# QueenSchematics.net
KiCad netlist of a schematic drawn in EAGLE
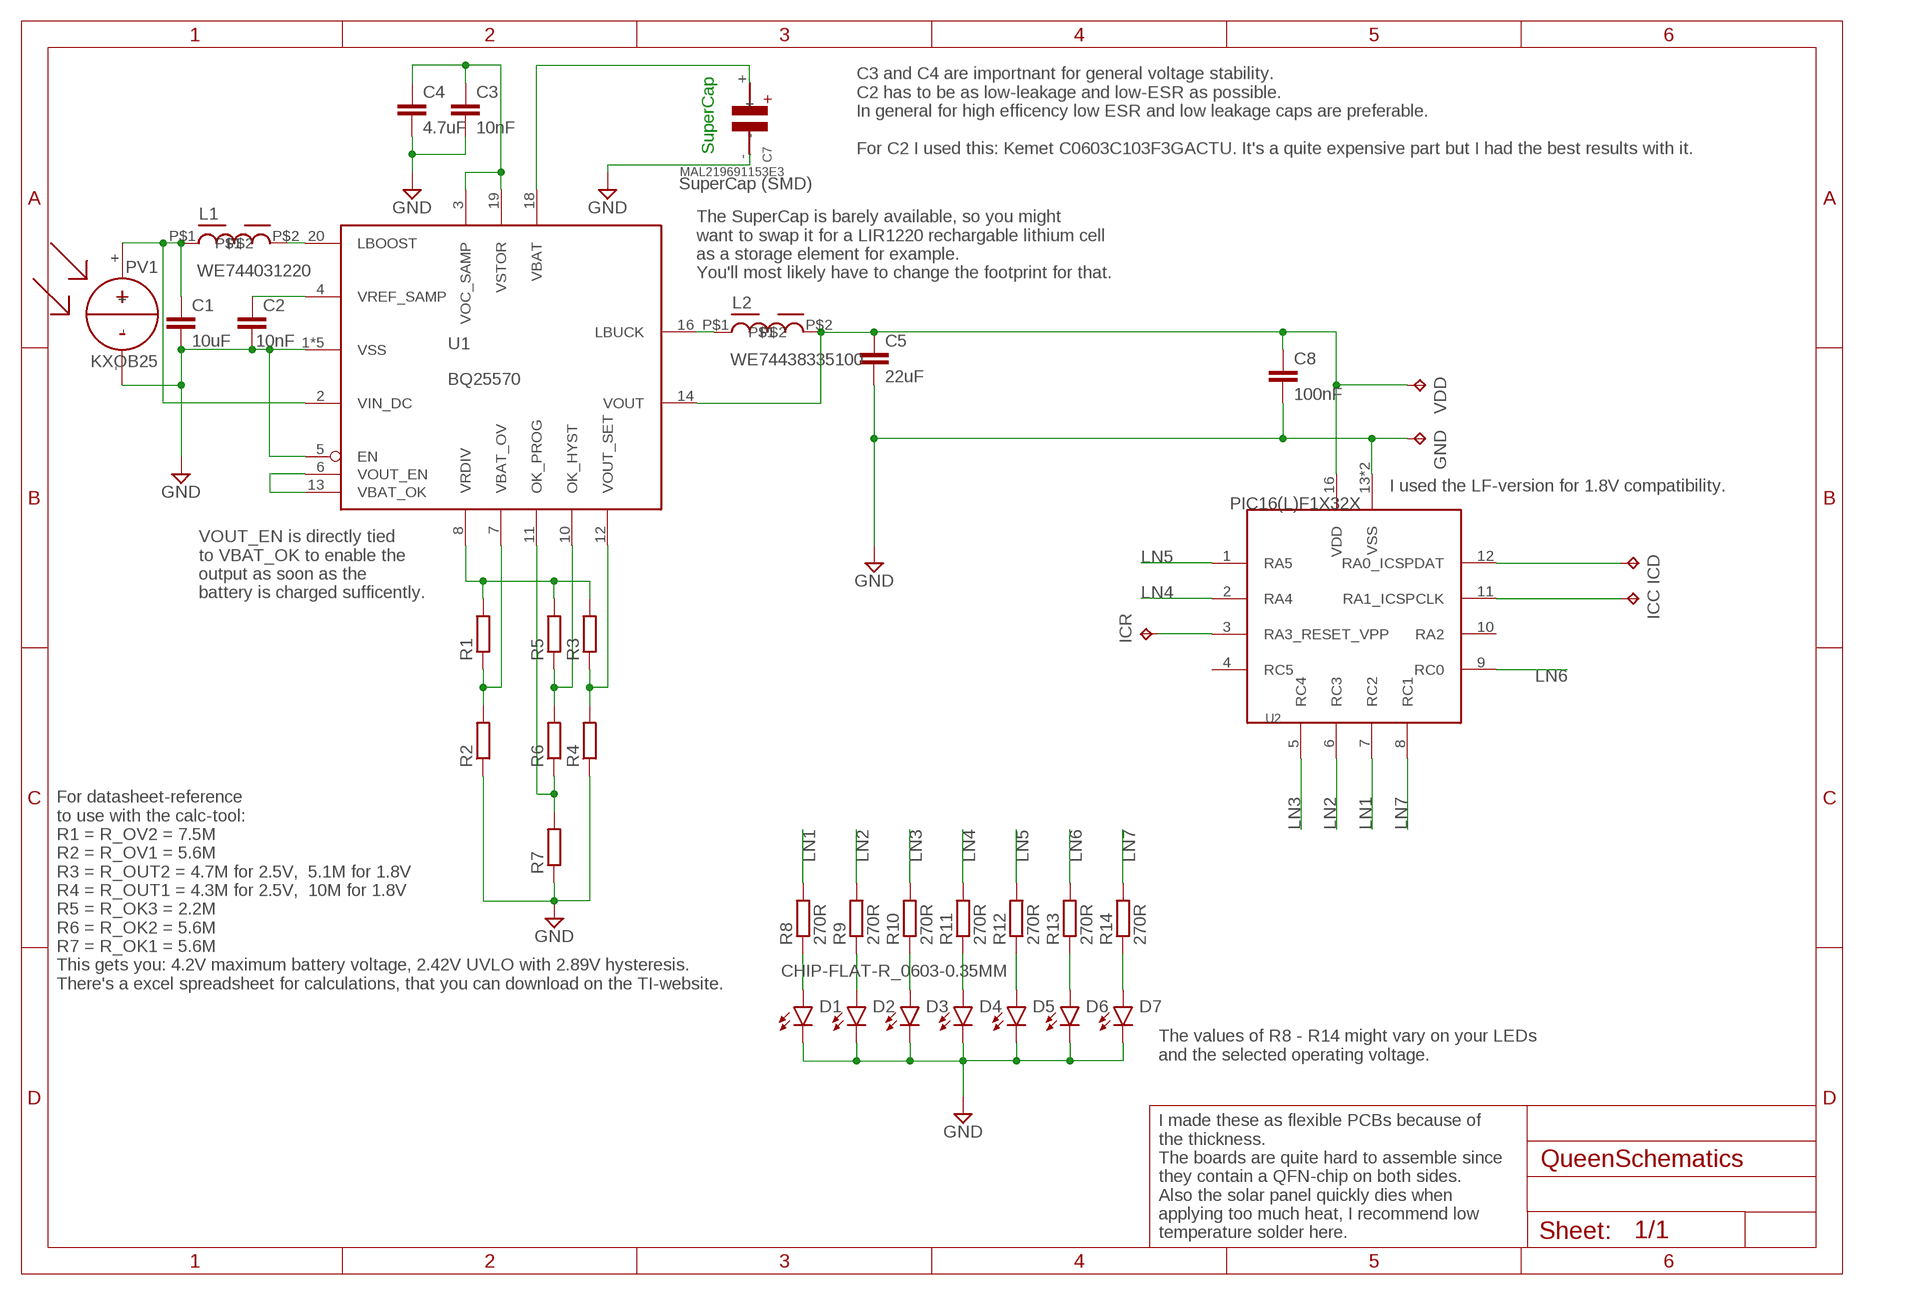
[diagram p0: schematic, sheet 1]

(export (version "E")
  (design (tool "Eeschema 10.0.6"))
  (components
    (comp (ref "C1")
      (value "10uF")
      (footprint "eagle-import:C0603K")
      (libsource (lib "eagle-import") (part "C-EUC0603K"))
    )
    (comp (ref "C2")
      (value "10nF")
      (footprint "eagle-import:C0603K")
      (libsource (lib "eagle-import") (part "C-EUC0603K"))
    )
    (comp (ref "C3")
      (value "10nF")
      (footprint "eagle-import:C0603K")
      (libsource (lib "eagle-import") (part "C-EUC0603K"))
    )
    (comp (ref "C4")
      (value "4.7uF")
      (footprint "eagle-import:C0603K")
      (libsource (lib "eagle-import") (part "C-EUC0603K"))
    )
    (comp (ref "C5")
      (value "22uF")
      (footprint "eagle-import:C0603K")
      (libsource (lib "eagle-import") (part "C-EUC0603K"))
    )
    (comp (ref "C7")
      (value "MAL219691153E3")
      (footprint "eagle-import:MAL219691153E2")
      (libsource (lib "eagle-import") (part "MAL21969115MAL219691153E2"))
    )
    (comp (ref "C8")
      (value "100nF")
      (footprint "eagle-import:C0603K")
      (libsource (lib "eagle-import") (part "C-EUC0603K"))
    )
    (comp (ref "D1")
      (value "CHIP-FLAT-R_0603-0.35MM")
      (footprint "eagle-import:LEDC1608X35N")
      (libsource (lib "eagle-import") (part "CHIP-FLAT-R_0603-0.35MM"))
    )
    (comp (ref "D2")
      (value "CHIP-FLAT-R_0603-0.35MM")
      (footprint "eagle-import:LEDC1608X35N")
      (libsource (lib "eagle-import") (part "CHIP-FLAT-R_0603-0.35MM"))
    )
    (comp (ref "D3")
      (value "CHIP-FLAT-R_0603-0.35MM")
      (footprint "eagle-import:LEDC1608X35N")
      (libsource (lib "eagle-import") (part "CHIP-FLAT-R_0603-0.35MM"))
    )
    (comp (ref "D4")
      (value "CHIP-FLAT-R_0603-0.35MM")
      (footprint "eagle-import:LEDC1608X35N")
      (libsource (lib "eagle-import") (part "CHIP-FLAT-R_0603-0.35MM"))
    )
    (comp (ref "D5")
      (value "CHIP-FLAT-R_0603-0.35MM")
      (footprint "eagle-import:LEDC1608X35N")
      (libsource (lib "eagle-import") (part "CHIP-FLAT-R_0603-0.35MM"))
    )
    (comp (ref "D6")
      (value "CHIP-FLAT-R_0603-0.35MM")
      (footprint "eagle-import:LEDC1608X35N")
      (libsource (lib "eagle-import") (part "CHIP-FLAT-R_0603-0.35MM"))
    )
    (comp (ref "D7")
      (value "CHIP-FLAT-R_0603-0.35MM")
      (footprint "eagle-import:LEDC1608X35N")
      (libsource (lib "eagle-import") (part "CHIP-FLAT-R_0603-0.35MM"))
    )
    (comp (ref "GND")
      (value "TPTP06SQ")
      (footprint "eagle-import:TP06SQ")
      (libsource (lib "eagle-import") (part "TPTP06SQ"))
    )
    (comp (ref "ICC")
      (value "TPTP06SQ")
      (footprint "eagle-import:TP06SQ")
      (libsource (lib "eagle-import") (part "TPTP06SQ"))
    )
    (comp (ref "ICD")
      (value "TPTP06SQ")
      (footprint "eagle-import:TP06SQ")
      (libsource (lib "eagle-import") (part "TPTP06SQ"))
    )
    (comp (ref "ICR")
      (value "TPTP06SQ")
      (footprint "eagle-import:TP06SQ")
      (libsource (lib "eagle-import") (part "TPTP06SQ"))
    )
    (comp (ref "L1")
      (value "WE744031220")
      (footprint "eagle-import:WE744031220")
      (libsource (lib "eagle-import") (part "WE744031220"))
    )
    (comp (ref "L2")
      (value "WE74438335100")
      (footprint "eagle-import:WE74438335100")
      (libsource (lib "eagle-import") (part "WE74438335100"))
    )
    (comp (ref "PV1")
      (value "KXOB25")
      (footprint "eagle-import:KXOB25")
      (libsource (lib "eagle-import") (part "KXOB25"))
    )
    (comp (ref "R1")
      (value "R-EU_R0603")
      (footprint "eagle-import:R0603")
      (libsource (lib "eagle-import") (part "R-EU_R0603"))
    )
    (comp (ref "R2")
      (value "R-EU_R0603")
      (footprint "eagle-import:R0603")
      (libsource (lib "eagle-import") (part "R-EU_R0603"))
    )
    (comp (ref "R3")
      (value "R-EU_R0603")
      (footprint "eagle-import:R0603")
      (libsource (lib "eagle-import") (part "R-EU_R0603"))
    )
    (comp (ref "R4")
      (value "R-EU_R0603")
      (footprint "eagle-import:R0603")
      (libsource (lib "eagle-import") (part "R-EU_R0603"))
    )
    (comp (ref "R5")
      (value "R-EU_R0603")
      (footprint "eagle-import:R0603")
      (libsource (lib "eagle-import") (part "R-EU_R0603"))
    )
    (comp (ref "R6")
      (value "R-EU_R0603")
      (footprint "eagle-import:R0603")
      (libsource (lib "eagle-import") (part "R-EU_R0603"))
    )
    (comp (ref "R7")
      (value "R-EU_R0603")
      (footprint "eagle-import:R0603")
      (libsource (lib "eagle-import") (part "R-EU_R0603"))
    )
    (comp (ref "R8")
      (value "270R")
      (footprint "eagle-import:R0603")
      (libsource (lib "eagle-import") (part "R-EU_R0603"))
    )
    (comp (ref "R9")
      (value "270R")
      (footprint "eagle-import:R0603")
      (libsource (lib "eagle-import") (part "R-EU_R0603"))
    )
    (comp (ref "R10")
      (value "270R")
      (footprint "eagle-import:R0603")
      (libsource (lib "eagle-import") (part "R-EU_R0603"))
    )
    (comp (ref "R11")
      (value "270R")
      (footprint "eagle-import:R0603")
      (libsource (lib "eagle-import") (part "R-EU_R0603"))
    )
    (comp (ref "R12")
      (value "270R")
      (footprint "eagle-import:R0603")
      (libsource (lib "eagle-import") (part "R-EU_R0603"))
    )
    (comp (ref "R13")
      (value "270R")
      (footprint "eagle-import:R0603")
      (libsource (lib "eagle-import") (part "R-EU_R0603"))
    )
    (comp (ref "R14")
      (value "270R")
      (footprint "eagle-import:R0603")
      (libsource (lib "eagle-import") (part "R-EU_R0603"))
    )
    (comp (ref "U1")
      (value "BQ25570")
      (footprint "eagle-import:QFN50P350X350X90-21T205N")
      (libsource (lib "eagle-import") (part "BQ25570"))
    )
    (comp (ref "U2")
      (value "PIC16(L)F1X32X")
      (footprint "eagle-import:QFN65P400X400X50-17T260N")
      (libsource (lib "eagle-import") (part "PIC16(L)F1X32X"))
    )
    (comp (ref "VDD")
      (value "TPTP06SQ")
      (footprint "eagle-import:TP06SQ")
      (libsource (lib "eagle-import") (part "TPTP06SQ"))
    )
  )
  (nets
    (net (code "1") (name "/LN1") (class "Default")
      (node (ref "R8") (pin "2") (pinfunction "2_2") (pintype "passive"))
      (node (ref "U2") (pin "7") (pinfunction "RC2_7") (pintype "bidirectional"))
    )
    (net (code "2") (name "/LN2") (class "Default")
      (node (ref "R9") (pin "2") (pinfunction "2_2") (pintype "passive"))
      (node (ref "U2") (pin "6") (pinfunction "RC3_6") (pintype "bidirectional"))
    )
    (net (code "3") (name "/LN3") (class "Default")
      (node (ref "R10") (pin "2") (pinfunction "2_2") (pintype "passive"))
      (node (ref "U2") (pin "5") (pinfunction "RC4_5") (pintype "bidirectional"))
    )
    (net (code "4") (name "/LN4") (class "Default")
      (node (ref "R11") (pin "2") (pinfunction "2_2") (pintype "passive"))
      (node (ref "U2") (pin "2") (pinfunction "RA4_2") (pintype "bidirectional"))
    )
    (net (code "5") (name "/LN5") (class "Default")
      (node (ref "R12") (pin "2") (pinfunction "2_2") (pintype "passive"))
      (node (ref "U2") (pin "1") (pinfunction "RA5_1") (pintype "bidirectional"))
    )
    (net (code "6") (name "/LN6") (class "Default")
      (node (ref "R13") (pin "2") (pinfunction "2_2") (pintype "passive"))
      (node (ref "U2") (pin "9") (pinfunction "RC0_9") (pintype "bidirectional"))
    )
    (net (code "7") (name "/LN7") (class "Default")
      (node (ref "R14") (pin "2") (pinfunction "2_2") (pintype "passive"))
      (node (ref "U2") (pin "8") (pinfunction "RC1_8") (pintype "bidirectional"))
    )
    (net (code "8") (name "GND") (class "Default")
      (node (ref "C1") (pin "2") (pinfunction "2_2") (pintype "passive"))
      (node (ref "C2") (pin "2") (pinfunction "2_2") (pintype "passive"))
      (node (ref "C3") (pin "2") (pinfunction "2_2") (pintype "passive"))
      (node (ref "C4") (pin "2") (pinfunction "2_2") (pintype "passive"))
      (node (ref "C5") (pin "2") (pinfunction "2_2") (pintype "passive"))
      (node (ref "C7") (pin "-") (pinfunction "-_-") (pintype "bidirectional"))
      (node (ref "C8") (pin "2") (pinfunction "2_2") (pintype "passive"))
      (node (ref "D1") (pin "C") (pinfunction "C_C") (pintype "passive"))
      (node (ref "D2") (pin "C") (pinfunction "C_C") (pintype "passive"))
      (node (ref "D3") (pin "C") (pinfunction "C_C") (pintype "passive"))
      (node (ref "D4") (pin "C") (pinfunction "C_C") (pintype "passive"))
      (node (ref "D5") (pin "C") (pinfunction "C_C") (pintype "passive"))
      (node (ref "D6") (pin "C") (pinfunction "C_C") (pintype "passive"))
      (node (ref "D7") (pin "C") (pinfunction "C_C") (pintype "passive"))
      (node (ref "GND") (pin "TP") (pinfunction "TP_TP") (pintype "input"))
      (node (ref "PV1") (pin "-") (pinfunction "-_-") (pintype "bidirectional"))
      (node (ref "R2") (pin "1") (pinfunction "1_1") (pintype "passive"))
      (node (ref "R4") (pin "1") (pinfunction "1_1") (pintype "passive"))
      (node (ref "R7") (pin "1") (pinfunction "1_1") (pintype "passive"))
      (node (ref "U1") (pin "1") (pinfunction "VSS_1") (pintype "bidirectional"))
      (node (ref "U1") (pin "15") (pinfunction "VSS_15") (pintype "bidirectional"))
      (node (ref "U1") (pin "17") (pinfunction "VSS_17") (pintype "bidirectional"))
      (node (ref "U1") (pin "21") (pinfunction "VSS_21") (pintype "bidirectional"))
      (node (ref "U1") (pin "5") (pinfunction "EN_5") (pintype "input"))
      (node (ref "U1") (pin "9") (pinfunction "VSS_9") (pintype "bidirectional"))
      (node (ref "U2") (pin "13") (pinfunction "VSS_13") (pintype "bidirectional"))
      (node (ref "U2") (pin "17") (pinfunction "VSS_17") (pintype "bidirectional"))
    )
    (net (code "9") (name "Net-(D1-PadA)") (class "Default")
      (node (ref "D1") (pin "A") (pinfunction "A_A") (pintype "passive"))
      (node (ref "R8") (pin "1") (pinfunction "1_1") (pintype "passive"))
    )
    (net (code "10") (name "Net-(D2-PadA)") (class "Default")
      (node (ref "D2") (pin "A") (pinfunction "A_A") (pintype "passive"))
      (node (ref "R9") (pin "1") (pinfunction "1_1") (pintype "passive"))
    )
    (net (code "11") (name "Net-(D3-PadA)") (class "Default")
      (node (ref "D3") (pin "A") (pinfunction "A_A") (pintype "passive"))
      (node (ref "R10") (pin "1") (pinfunction "1_1") (pintype "passive"))
    )
    (net (code "12") (name "Net-(D4-PadA)") (class "Default")
      (node (ref "D4") (pin "A") (pinfunction "A_A") (pintype "passive"))
      (node (ref "R11") (pin "1") (pinfunction "1_1") (pintype "passive"))
    )
    (net (code "13") (name "Net-(D5-PadA)") (class "Default")
      (node (ref "D5") (pin "A") (pinfunction "A_A") (pintype "passive"))
      (node (ref "R12") (pin "1") (pinfunction "1_1") (pintype "passive"))
    )
    (net (code "14") (name "Net-(D6-PadA)") (class "Default")
      (node (ref "D6") (pin "A") (pinfunction "A_A") (pintype "passive"))
      (node (ref "R13") (pin "1") (pinfunction "1_1") (pintype "passive"))
    )
    (net (code "15") (name "Net-(D7-PadA)") (class "Default")
      (node (ref "D7") (pin "A") (pinfunction "A_A") (pintype "passive"))
      (node (ref "R14") (pin "1") (pinfunction "1_1") (pintype "passive"))
    )
    (net (code "16") (name "Net-(U1-LBOOST)") (class "Default")
      (node (ref "L1") (pin "P$2") (pinfunction "P$2_P$2") (pintype "bidirectional"))
      (node (ref "U1") (pin "20") (pinfunction "LBOOST_20") (pintype "bidirectional"))
    )
    (net (code "17") (name "Net-(U1-LBUCK)") (class "Default")
      (node (ref "L2") (pin "P$1") (pinfunction "P$1_P$1") (pintype "bidirectional"))
      (node (ref "U1") (pin "16") (pinfunction "LBUCK_16") (pintype "bidirectional"))
    )
    (net (code "18") (name "Net-(U1-OK_HYST)") (class "Default")
      (node (ref "R5") (pin "1") (pinfunction "1_1") (pintype "passive"))
      (node (ref "R6") (pin "2") (pinfunction "2_2") (pintype "passive"))
      (node (ref "U1") (pin "10") (pinfunction "OK_HYST_10") (pintype "bidirectional"))
    )
    (net (code "19") (name "Net-(U1-OK_PROG)") (class "Default")
      (node (ref "R6") (pin "1") (pinfunction "1_1") (pintype "passive"))
      (node (ref "R7") (pin "2") (pinfunction "2_2") (pintype "passive"))
      (node (ref "U1") (pin "11") (pinfunction "OK_PROG_11") (pintype "bidirectional"))
    )
    (net (code "20") (name "Net-(U1-VBAT)") (class "Default")
      (node (ref "C7") (pin "+") (pinfunction "+_+") (pintype "bidirectional"))
      (node (ref "U1") (pin "18") (pinfunction "VBAT_18") (pintype "bidirectional"))
    )
    (net (code "21") (name "Net-(U1-VBAT_OK)") (class "Default")
      (node (ref "U1") (pin "13") (pinfunction "VBAT_OK_13") (pintype "bidirectional"))
      (node (ref "U1") (pin "6") (pinfunction "VOUT_EN_6") (pintype "bidirectional"))
    )
    (net (code "22") (name "Net-(U1-VBAT_OV)") (class "Default")
      (node (ref "R1") (pin "1") (pinfunction "1_1") (pintype "passive"))
      (node (ref "R2") (pin "2") (pinfunction "2_2") (pintype "passive"))
      (node (ref "U1") (pin "7") (pinfunction "VBAT_OV_7") (pintype "bidirectional"))
    )
    (net (code "23") (name "Net-(U1-VIN_DC)") (class "Default")
      (node (ref "C1") (pin "1") (pinfunction "1_1") (pintype "passive"))
      (node (ref "L1") (pin "P$1") (pinfunction "P$1_P$1") (pintype "bidirectional"))
      (node (ref "PV1") (pin "+") (pinfunction "+_+") (pintype "bidirectional"))
      (node (ref "U1") (pin "2") (pinfunction "VIN_DC_2") (pintype "bidirectional"))
    )
    (net (code "24") (name "Net-(U1-VOC_SAMP)") (class "Default")
      (node (ref "C3") (pin "1") (pinfunction "1_1") (pintype "passive"))
      (node (ref "C4") (pin "1") (pinfunction "1_1") (pintype "passive"))
      (node (ref "U1") (pin "19") (pinfunction "VSTOR_19") (pintype "bidirectional"))
      (node (ref "U1") (pin "3") (pinfunction "VOC_SAMP_3") (pintype "bidirectional"))
    )
    (net (code "25") (name "Net-(U1-VOUT)") (class "Default")
      (node (ref "C5") (pin "1") (pinfunction "1_1") (pintype "passive"))
      (node (ref "C8") (pin "1") (pinfunction "1_1") (pintype "passive"))
      (node (ref "L2") (pin "P$2") (pinfunction "P$2_P$2") (pintype "bidirectional"))
      (node (ref "U1") (pin "14") (pinfunction "VOUT_14") (pintype "bidirectional"))
      (node (ref "U2") (pin "16") (pinfunction "VDD_16") (pintype "power_in"))
      (node (ref "VDD") (pin "TP") (pinfunction "TP_TP") (pintype "input"))
    )
    (net (code "26") (name "Net-(U1-VOUT_SET)") (class "Default")
      (node (ref "R3") (pin "1") (pinfunction "1_1") (pintype "passive"))
      (node (ref "R4") (pin "2") (pinfunction "2_2") (pintype "passive"))
      (node (ref "U1") (pin "12") (pinfunction "VOUT_SET_12") (pintype "bidirectional"))
    )
    (net (code "27") (name "Net-(U1-VRDIV)") (class "Default")
      (node (ref "R1") (pin "2") (pinfunction "2_2") (pintype "passive"))
      (node (ref "R3") (pin "2") (pinfunction "2_2") (pintype "passive"))
      (node (ref "R5") (pin "2") (pinfunction "2_2") (pintype "passive"))
      (node (ref "U1") (pin "8") (pinfunction "VRDIV_8") (pintype "bidirectional"))
    )
    (net (code "28") (name "Net-(U1-VREF_SAMP)") (class "Default")
      (node (ref "C2") (pin "1") (pinfunction "1_1") (pintype "passive"))
      (node (ref "U1") (pin "4") (pinfunction "VREF_SAMP_4") (pintype "bidirectional"))
    )
    (net (code "29") (name "Net-(U2-RA0_ICSPDAT)") (class "Default")
      (node (ref "ICD") (pin "TP") (pinfunction "TP_TP") (pintype "input"))
      (node (ref "U2") (pin "12") (pinfunction "RA0_ICSPDAT_12") (pintype "bidirectional"))
    )
    (net (code "30") (name "Net-(U2-RA1_ICSPCLK)") (class "Default")
      (node (ref "ICC") (pin "TP") (pinfunction "TP_TP") (pintype "input"))
      (node (ref "U2") (pin "11") (pinfunction "RA1_ICSPCLK_11") (pintype "bidirectional"))
    )
    (net (code "31") (name "Net-(U2-RA3_RESET_VPP)") (class "Default")
      (node (ref "ICR") (pin "TP") (pinfunction "TP_TP") (pintype "input"))
      (node (ref "U2") (pin "3") (pinfunction "RA3_RESET_VPP_3") (pintype "bidirectional"))
    )
    (net (code "32") (name "unconnected-(U2-RA2-Pad10)") (class "Default")
      (node (ref "U2") (pin "10") (pinfunction "RA2_10") (pintype "bidirectional"))
    )
    (net (code "33") (name "unconnected-(U2-RC5-Pad4)") (class "Default")
      (node (ref "U2") (pin "4") (pinfunction "RC5_4") (pintype "bidirectional"))
    )
  )
)
